# GSM_SOM.net
KiCad netlist of a schematic drawn in Altium Designer
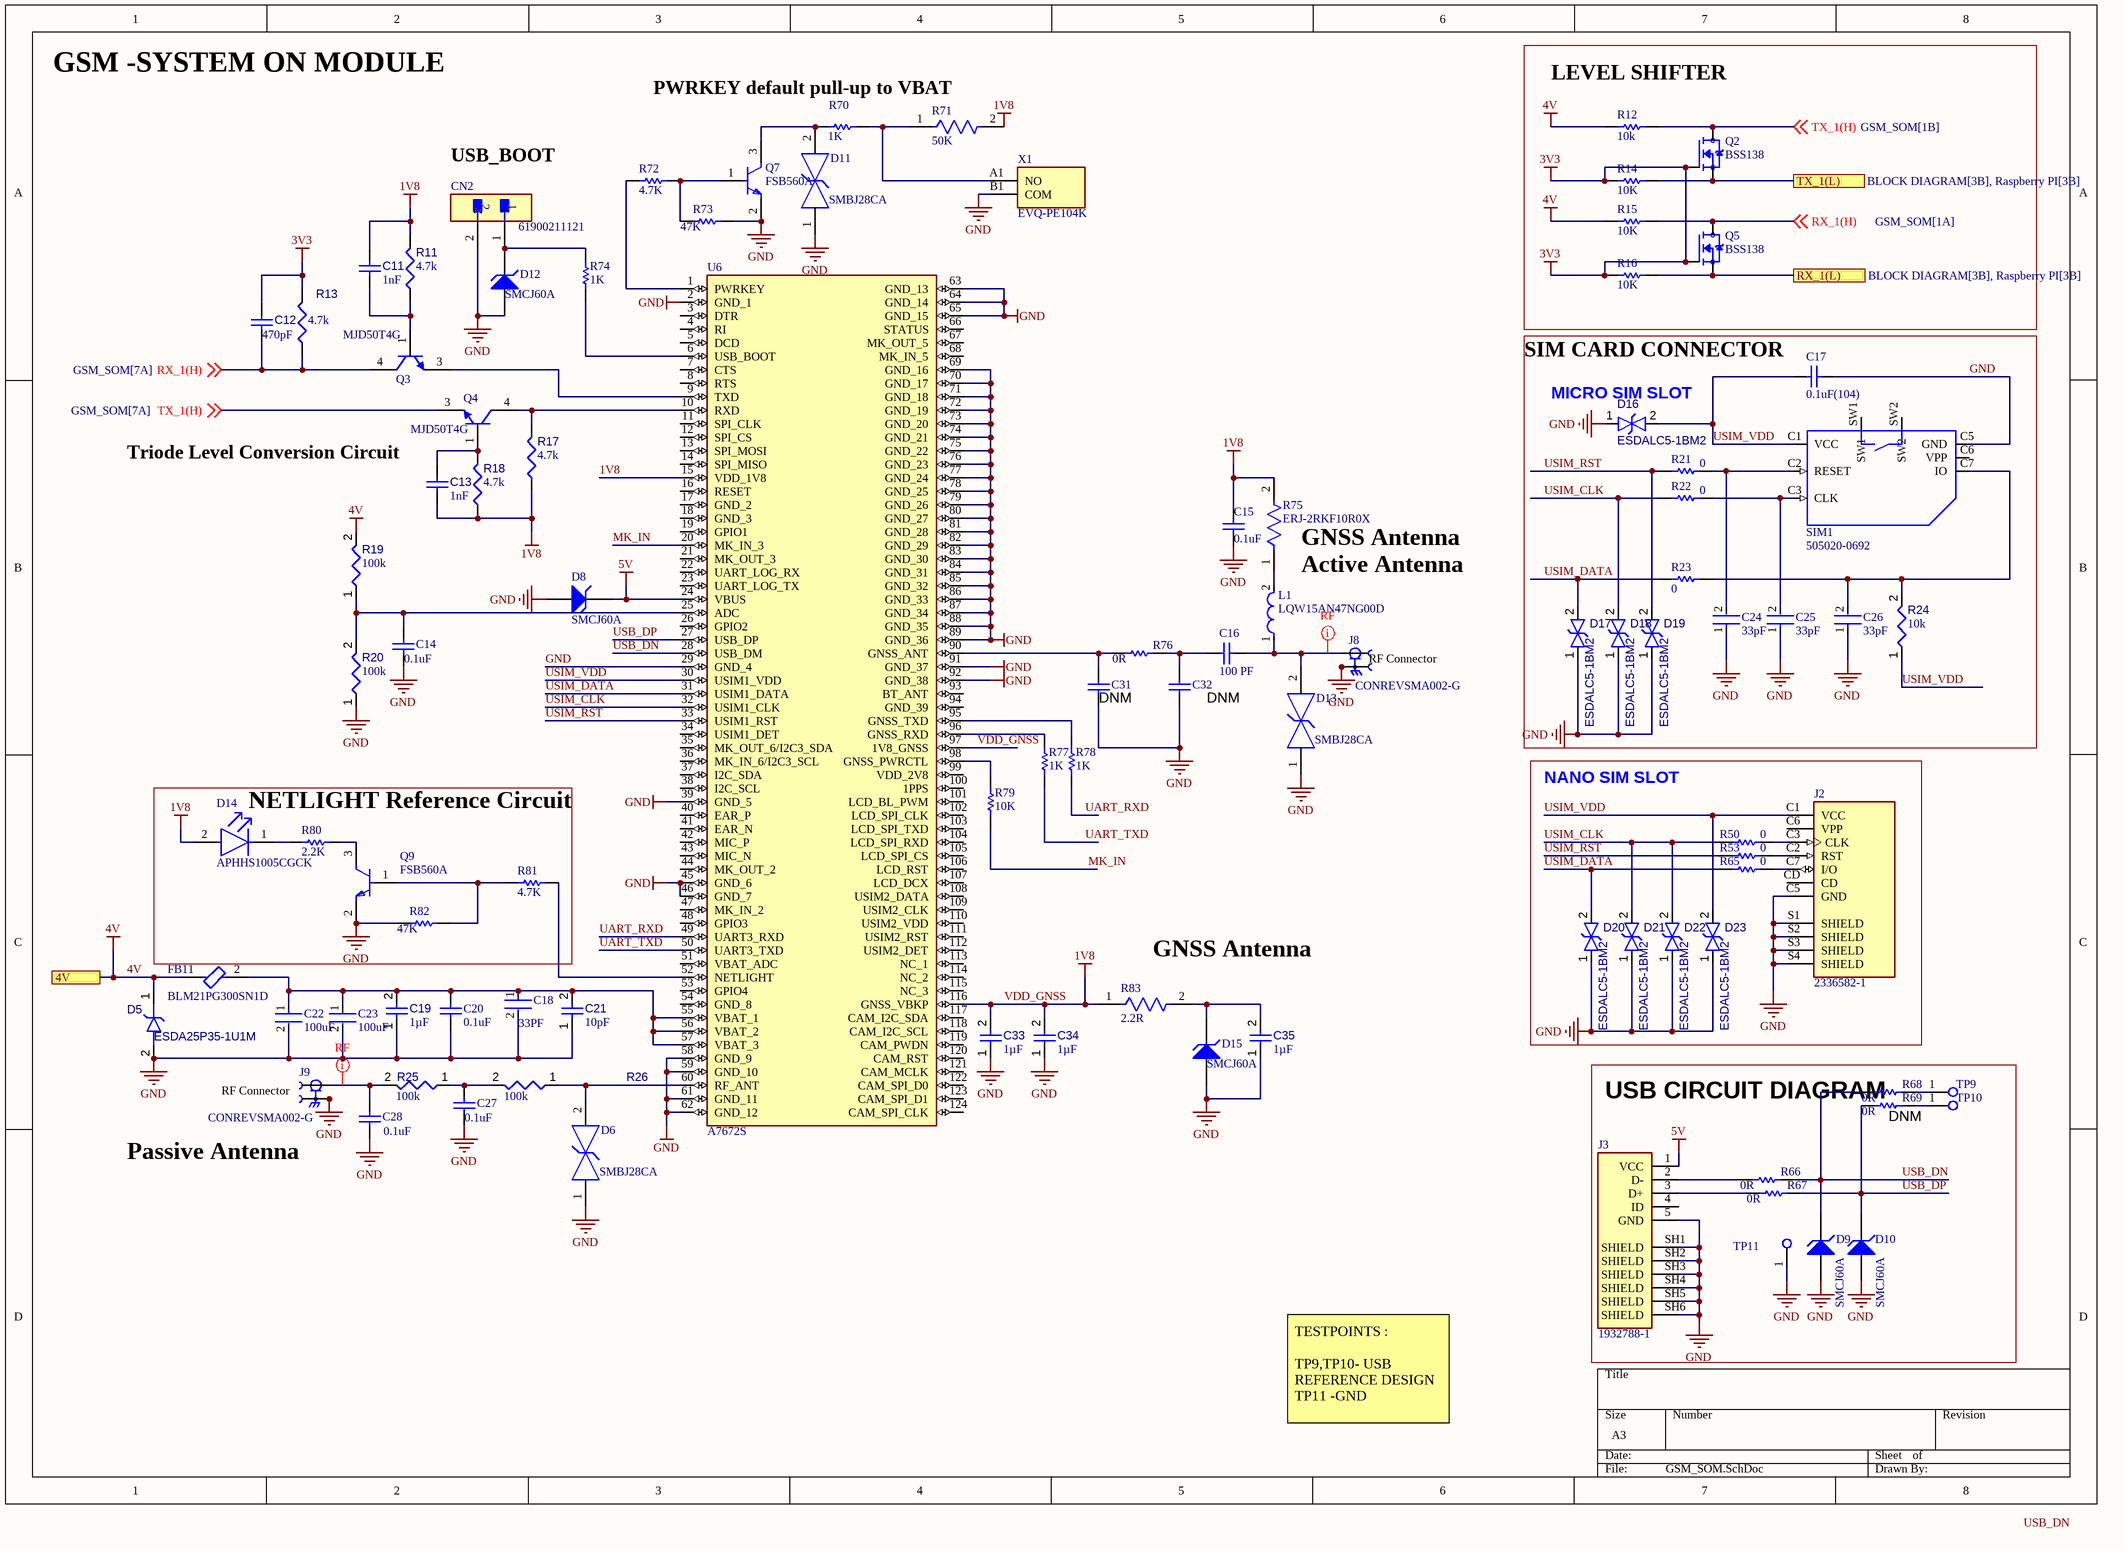
[diagram p0: GSM_SOM.SchDoc]

(export (version "E")
  (design (tool "Eeschema 10.0.6"))
  (components
    (comp (ref "C11")
      (value "1nF")
      (footprint "CAPC0402(1005)33_L")
      (description "Chip Capacitor, 1nF +/-20%, 50V, 0402, Thickness 0.33 mm")
      (fields (field (name "TOLERANCE") "10%") (field (name "Comment") "Capacitor 1nF +/-20% 50V 0402"))
      (libsource (lib "Bannari Amman Institute of Technology") (part "CAP-NP-2"))
    )
    (comp (ref "C12")
      (value "470pF")
      (footprint "CAPC0402(1005)60_L")
      (description "Chip Capacitor, 470pF +/-20%, 50V, 0402, Thickness 0.6 mm")
      (fields (field (name "TOLERANCE") "20%") (field (name "Comment") "Capacitor 470pF +/-20% 50V 0402"))
      (libsource (lib "Bannari Amman Institute of Technology") (part "CAP-NP-2"))
    )
    (comp (ref "C13")
      (value "1nF")
      (footprint "CAPC0402(1005)33_L")
      (description "Chip Capacitor, 1nF +/-20%, 50V, 0402, Thickness 0.33 mm")
      (fields (field (name "TOLERANCE") "10%") (field (name "Comment") "Capacitor 1nF +/-20% 50V 0402"))
      (libsource (lib "Bannari Amman Institute of Technology") (part "CAP-NP-2"))
    )
    (comp (ref "C14")
      (value "0.1uF")
      (footprint "CAPC1005X55X30LL05T10")
      (fields (field (name "MANUFACTURER") "Kemet") (field (name "PART NUMBER") "C0402C104K4RACTU"))
      (libsource (lib "Altium Content Vault") (part "CAP"))
    )
    (comp (ref "C15")
      (value "0.1uF")
      (footprint "CAPC1005X55X30LL05T10")
      (fields (field (name "MANUFACTURER") "Kemet") (field (name "PART NUMBER") "C0402C104K4RACTU"))
      (libsource (lib "Altium Content Vault") (part "CAP"))
    )
    (comp (ref "C16")
      (value "100 PF")
      (footprint "CAPC1005X55X25ML05T10")
      (fields (field (name "MANUFACTURER") "Murata") (field (name "PART NUMBER") "GRM1555C1H101JA01D"))
      (libsource (lib "Altium Content Vault") (part "CAP"))
    )
    (comp (ref "C17")
      (value "0.1uF(104)")
      (footprint "CAPC1005X55X30LL05T10")
      (fields (field (name "MANUFACTURER") "Kemet") (field (name "PART NUMBER") "C0402C104K4RACTU"))
      (libsource (lib "Altium Content Vault") (part "CAP"))
    )
    (comp (ref "C18")
      (value "33PF")
      (footprint "FP-0402-L_1_0_1-W_0_5_0_1-IPC_A")
      (description "General Purpose Ceramic Capacitor, 0402, 33pF, 5%, C0G, 30ppm/°C, 50V")
      (fields (field (name "TOLERANCE") "5%") (field (name "VOLTAGE") "50V"))
      (libsource (lib "Altium Content Vault") (part "b4654b650e69147ec39a6b967a45e02"))
    )
    (comp (ref "C19")
      (value "1µF")
      (footprint "CAPC0402(1005)60_L")
      (description "Chip Capacitor, 1µF +/-20%, 10V, 0402, Thickness 0.6 mm")
      (fields (field (name "TOLERANCE") "10%") (field (name "Comment") "Capacitor 1µF +/-20% 10V 0402"))
      (libsource (lib "") (part "CAP-NP-2_1"))
    )
    (comp (ref "C20")
      (value "0.1uF")
      (footprint "CAPC1005X55X30LL05T10")
      (fields (field (name "MANUFACTURER") "Kemet") (field (name "PART NUMBER") "C0402C104K4RACTU"))
      (libsource (lib "Altium Content Vault") (part "CAP"))
    )
    (comp (ref "C21")
      (value "10pF")
      (footprint "CAPC1005X55X30LL05T10")
      (description "Chip Capacitor, 10 pF, +/- 0.25 pF, 50 V, 0402 (1005 Metric)")
      (fields
        (field (name "TOLERANCE") "0.25%")
        (field (name "Comment") "Capacitor 10 pF +/- 0.25 pF 50 V 0402")
      )
      (libsource (lib "") (part "CAP-NP-2_1"))
    )
    (comp (ref "C22")
      (value "100uF")
      (footprint "FP-GRM32-0_3-MFG")
      (description "CAP CER 100UF 6.3V X5R 1210")
      (fields
        (field (name "OCTOPART") "https://octopart.com/grm32er60j107me20l-murata-197007")
        (field (name "3DS PART NUMBER") "220-00002")
      )
      (libsource (lib "Altium Content Vault") (part "11868f565c42a9108669ba33697ecf6"))
    )
    (comp (ref "C23")
      (value "100uF")
      (footprint "FP-GRM32-0_3-MFG")
      (description "CAP CER 100UF 6.3V X5R 1210")
      (fields
        (field (name "OCTOPART") "https://octopart.com/grm32er60j107me20l-murata-197007")
        (field (name "3DS PART NUMBER") "220-00002")
      )
      (libsource (lib "Altium Content Vault") (part "11868f565c42a9108669ba33697ecf6"))
    )
    (comp (ref "C24")
      (value "33pF")
      (footprint "FP-0402-L_1_0_1-W_0_5_0_1-IPC_A")
      (description "General Purpose Ceramic Capacitor, 0402, 33pF, 5%, C0G, 30ppm/°C, 50V")
      (fields (field (name "TOLERANCE") "5%") (field (name "VOLTAGE") "50V"))
      (libsource (lib "Altium Content Vault") (part "b4654b650e69147ec39a6b967a45e02"))
    )
    (comp (ref "C25")
      (value "33pF")
      (footprint "FP-0402-L_1_0_1-W_0_5_0_1-IPC_A")
      (description "General Purpose Ceramic Capacitor, 0402, 33pF, 5%, C0G, 30ppm/°C, 50V")
      (fields (field (name "TOLERANCE") "5%") (field (name "VOLTAGE") "50V"))
      (libsource (lib "Altium Content Vault") (part "b4654b650e69147ec39a6b967a45e02"))
    )
    (comp (ref "C26")
      (value "33pF")
      (footprint "FP-0402-L_1_0_1-W_0_5_0_1-IPC_A")
      (description "General Purpose Ceramic Capacitor, 0402, 33pF, 5%, C0G, 30ppm/°C, 50V")
      (fields (field (name "TOLERANCE") "5%") (field (name "VOLTAGE") "50V"))
      (libsource (lib "Altium Content Vault") (part "b4654b650e69147ec39a6b967a45e02"))
    )
    (comp (ref "C27")
      (value "0.1uF")
      (footprint "CAPC1005X55X30LL05T10")
      (fields (field (name "MANUFACTURER") "Kemet") (field (name "PART NUMBER") "C0402C104K4RACTU"))
      (libsource (lib "Altium Content Vault") (part "CAP"))
    )
    (comp (ref "C28")
      (value "0.1uF")
      (footprint "CAPC1005X55X30LL05T10")
      (fields (field (name "MANUFACTURER") "Kemet") (field (name "PART NUMBER") "C0402C104K4RACTU"))
      (libsource (lib "Altium Content Vault") (part "CAP"))
    )
    (comp (ref "C31")
      (value "0.1uF")
      (footprint "CAPC1005X55X30LL05T10")
      (fields (field (name "MANUFACTURER") "Kemet") (field (name "PART NUMBER") "C0402C104K4RACTU"))
      (libsource (lib "Altium Content Vault") (part "CAP"))
    )
    (comp (ref "C32")
      (value "0.1uF")
      (footprint "CAPC1005X55X30LL05T10")
      (fields (field (name "MANUFACTURER") "Kemet") (field (name "PART NUMBER") "C0402C104K4RACTU"))
      (libsource (lib "Altium Content Vault") (part "CAP"))
    )
    (comp (ref "C33")
      (value "1µF")
      (footprint "CAPC0402(1005)60_L")
      (description "Chip Capacitor, 1µF +/-20%, 10V, 0402, Thickness 0.6 mm")
      (fields (field (name "TOLERANCE") "10%") (field (name "Comment") "Capacitor 1µF +/-20% 10V 0402"))
      (libsource (lib "") (part "CAP-NP-2_1"))
    )
    (comp (ref "C34")
      (value "1µF")
      (footprint "CAPC0402(1005)60_L")
      (description "Chip Capacitor, 1µF +/-20%, 10V, 0402, Thickness 0.6 mm")
      (fields (field (name "TOLERANCE") "10%") (field (name "Comment") "Capacitor 1µF +/-20% 10V 0402"))
      (libsource (lib "") (part "CAP-NP-2_1"))
    )
    (comp (ref "C35")
      (value "1µF")
      (footprint "CAPC0402(1005)60_L")
      (description "Chip Capacitor, 1µF +/-20%, 10V, 0402, Thickness 0.6 mm")
      (fields (field (name "TOLERANCE") "10%") (field (name "Comment") "Capacitor 1µF +/-20% 10V 0402"))
      (libsource (lib "") (part "CAP-NP-2_1"))
    )
    (comp (ref "CN2")
      (value "61900211121")
      (footprint "FP-61900211121-MFG")
      (description "CONN HEADER VERT 2POS 2.54MM")
      (libsource (lib "Altium Content Vault") (part "3bc925449376181038e59eaffc5286c"))
    )
    (comp (ref "D5")
      (value "ESDA25P35-1U1M")
      (footprint "STM-QFN1610")
      (description "TVS DIODE 22V 41V 1610")
      (libsource (lib "Bannari Amman Institute of Technology") (part "D-TVS-AK-2"))
    )
    (comp (ref "D6")
      (value "SMBJ28CA")
      (footprint "FP-SMBJ-CA-MFG")
      (description "TVS DIODE 28V 45.4V DO214AA")
      (fields
        (field (name "MANUFACTURER") "Littelfuse Inc")
        (field (name "OCTOPART") "https://octopart.com/smbj28ca-littelfuse-350757")
      )
      (libsource (lib "Altium Content Vault") (part "89c663e49c8877d2c9d183c2997548d"))
    )
    (comp (ref "D8")
      (value "SMCJ60A")
      (footprint "LFUS-DO-214AB-2_V")
      (fields (field (name "MANUFACTURER") "Littelfuse"))
      (libsource (lib "Altium Content Vault") (part "DZEN-AK-2"))
    )
    (comp (ref "D9")
      (value "SMCJ60A")
      (footprint "LFUS-DO-214AB-2_V")
      (fields (field (name "MANUFACTURER") "Littelfuse"))
      (libsource (lib "Altium Content Vault") (part "DZEN-AK-2"))
    )
    (comp (ref "D10")
      (value "SMCJ60A")
      (footprint "LFUS-DO-214AB-2_V")
      (fields (field (name "MANUFACTURER") "Littelfuse"))
      (libsource (lib "Altium Content Vault") (part "DZEN-AK-2"))
    )
    (comp (ref "D11")
      (value "SMBJ28CA")
      (footprint "FP-SMBJ-CA-MFG")
      (description "TVS DIODE 28V 45.4V DO214AA")
      (fields
        (field (name "MANUFACTURER") "Littelfuse Inc")
        (field (name "OCTOPART") "https://octopart.com/smbj28ca-littelfuse-350757")
      )
      (libsource (lib "Altium Content Vault") (part "89c663e49c8877d2c9d183c2997548d"))
    )
    (comp (ref "D12")
      (value "SMCJ60A")
      (footprint "LFUS-DO-214AB-2_V")
      (fields (field (name "MANUFACTURER") "Littelfuse"))
      (libsource (lib "Altium Content Vault") (part "DZEN-AK-2"))
    )
    (comp (ref "D13")
      (value "SMBJ28CA")
      (footprint "FP-SMBJ-CA-MFG")
      (description "TVS DIODE 28V 45.4V DO214AA")
      (fields
        (field (name "MANUFACTURER") "Littelfuse Inc")
        (field (name "OCTOPART") "https://octopart.com/smbj28ca-littelfuse-350757")
      )
      (libsource (lib "Altium Content Vault") (part "89c663e49c8877d2c9d183c2997548d"))
    )
    (comp (ref "D14")
      (value "APHHS1005CGCK")
      (footprint "FP-APHHS1005CGCK-MFG")
      (description "LED GREEN CLEAR CHIP SMD")
      (libsource (lib "Altium Content Vault") (part "8706943c75ba83719d021d2fdc84c58"))
    )
    (comp (ref "D15")
      (value "SMCJ60A")
      (footprint "LFUS-DO-214AB-2_V")
      (fields (field (name "MANUFACTURER") "Littelfuse"))
      (libsource (lib "Altium Content Vault") (part "DZEN-AK-2"))
    )
    (comp (ref "D16")
      (value "ESDALC5-1BM2")
      (footprint "STM-SOD-882_V")
      (description "Single Line Low Capacitance Transil™, 5 V, -55 to 150 degC, 2-Pin SOD-882, RoHS, Tape and Reel")
      (libsource (lib "Bannari Amman Institute of Technology") (part "D-TVS-AA-2"))
    )
    (comp (ref "D17")
      (value "ESDALC5-1BM2")
      (footprint "STM-SOD-882_V")
      (description "Single Line Low Capacitance Transil™, 5 V, -55 to 150 degC, 2-Pin SOD-882, RoHS, Tape and Reel")
      (libsource (lib "Bannari Amman Institute of Technology") (part "D-TVS-AA-2"))
    )
    (comp (ref "D18")
      (value "ESDALC5-1BM2")
      (footprint "STM-SOD-882_V")
      (description "Single Line Low Capacitance Transil™, 5 V, -55 to 150 degC, 2-Pin SOD-882, RoHS, Tape and Reel")
      (libsource (lib "Bannari Amman Institute of Technology") (part "D-TVS-AA-2"))
    )
    (comp (ref "D19")
      (value "ESDALC5-1BM2")
      (footprint "STM-SOD-882_V")
      (description "Single Line Low Capacitance Transil™, 5 V, -55 to 150 degC, 2-Pin SOD-882, RoHS, Tape and Reel")
      (libsource (lib "Bannari Amman Institute of Technology") (part "D-TVS-AA-2"))
    )
    (comp (ref "D20")
      (value "ESDALC5-1BM2")
      (footprint "STM-SOD-882_V")
      (description "Single Line Low Capacitance Transil™, 5 V, -55 to 150 degC, 2-Pin SOD-882, RoHS, Tape and Reel")
      (libsource (lib "Bannari Amman Institute of Technology") (part "D-TVS-AA-2"))
    )
    (comp (ref "D21")
      (value "ESDALC5-1BM2")
      (footprint "STM-SOD-882_V")
      (description "Single Line Low Capacitance Transil™, 5 V, -55 to 150 degC, 2-Pin SOD-882, RoHS, Tape and Reel")
      (libsource (lib "Bannari Amman Institute of Technology") (part "D-TVS-AA-2"))
    )
    (comp (ref "D22")
      (value "ESDALC5-1BM2")
      (footprint "STM-SOD-882_V")
      (description "Single Line Low Capacitance Transil™, 5 V, -55 to 150 degC, 2-Pin SOD-882, RoHS, Tape and Reel")
      (libsource (lib "Bannari Amman Institute of Technology") (part "D-TVS-AA-2"))
    )
    (comp (ref "D23")
      (value "ESDALC5-1BM2")
      (footprint "STM-SOD-882_V")
      (description "Single Line Low Capacitance Transil™, 5 V, -55 to 150 degC, 2-Pin SOD-882, RoHS, Tape and Reel")
      (libsource (lib "Bannari Amman Institute of Technology") (part "D-TVS-AA-2"))
    )
    (comp (ref "FB1")
      (value "BLM21PG300SN1D")
      (footprint "FP-BLM21-0_2-t0_85-e0_5-d-MFG")
      (description "Chip Ferrite Bead, 0805, 30Ω @ 100MHz, 0.014Ω, , 4A")
      (fields (field (name "TOLERANCE") "25%"))
      (libsource (lib "Altium Content Vault") (part "5f30dd21d616792df468990f7003faa"))
    )
    (comp (ref "J2")
      (value "2336582-1")
      (footprint "TE_2336582-1")
      (description "PUSH-PUSH NANO SIM CONNECTOR")
      (libsource (lib "2336582-1") (part "2336582-1"))
    )
    (comp (ref "J3")
      (value "1932788-1")
      (footprint "TE_1932788-1")
      (libsource (lib "1932788-1") (part "1932788-1"))
    )
    (comp (ref "J8")
      (value "CONREVSMA002-G")
      (footprint "LINX_CONREVSMA002-G")
      (description "RP-SMA Female Right-Angle Through-Hole Mount Connector, Gold")
      (fields (field (name "MF") "Linx Technologies"))
      (libsource (lib "") (part "CONREVSMA002-G_1"))
    )
    (comp (ref "J9")
      (value "CONREVSMA002-G")
      (footprint "LINX_CONREVSMA002-G")
      (description "RP-SMA Female Right-Angle Through-Hole Mount Connector, Gold")
      (fields (field (name "MF") "Linx Technologies"))
      (libsource (lib "CONREVSMA002-G") (part "CONREVSMA002-G"))
    )
    (comp (ref "L1")
      (value "LQW15AN47NG00D")
      (footprint "FP-LQW15AN_00-W0_5-0_1-MFG")
      (description "Wire Wound RF Inductor 47nH ±2% 210mA 1.08Ω 0402 (1005)")
      (fields (field (name "TOLERANCE") "2%"))
      (libsource (lib "Altium Content Vault") (part "725321dda6339637d4d059423bc1c3c"))
    )
    (comp (ref "Q2")
      (value "BSS138")
      (footprint "SOT95P240X111-3N")
      (description "N-Channel 50V 220mA (Ta) 360mW (Ta) Surface Mount SOT-23-3")
      (fields (field (name "MF") "ON Semiconductor"))
      (libsource (lib "BSS138") (part "BSS138"))
    )
    (comp (ref "Q3")
      (value "MJD50T4G")
      (footprint "ONSC-DPAK-3-369C-01_V")
      (description "High Voltage Power Transistor, 3-Pin DPAK, Pb-Free, Tape and Reel")
      (fields (field (name "MANUFACTURER") "On Semiconductor"))
      (libsource (lib "Altium Content Vault") (part "ONSC-NPN-B1E3C4-3"))
    )
    (comp (ref "Q4")
      (value "MJD50T4G")
      (footprint "ONSC-DPAK-3-369C-01_V")
      (description "High Voltage Power Transistor, 3-Pin DPAK, Pb-Free, Tape and Reel")
      (fields (field (name "MANUFACTURER") "On Semiconductor"))
      (libsource (lib "Altium Content Vault") (part "ONSC-NPN-B1E3C4-3"))
    )
    (comp (ref "Q5")
      (value "BSS138")
      (footprint "SOT95P240X111-3N")
      (description "N-Channel 50V 220mA (Ta) 360mW (Ta) Surface Mount SOT-23-3")
      (fields (field (name "MF") "ON Semiconductor"))
      (libsource (lib "BSS138") (part "BSS138"))
    )
    (comp (ref "Q7")
      (value "FSB560A")
      (footprint "FP-527AG-MFG")
      (description "FSB560A Bipolar Transistors - BJT NPN Transistor Low Saturation")
      (libsource (lib "Altium Content Vault") (part "b44e953556f554d0102664c7d152cb4"))
    )
    (comp (ref "Q9")
      (value "FSB560A")
      (footprint "FP-527AG-MFG")
      (description "FSB560A Bipolar Transistors - BJT NPN Transistor Low Saturation")
      (libsource (lib "Altium Content Vault") (part "b44e953556f554d0102664c7d152cb4"))
    )
    (comp (ref "R11")
      (value "4.7k")
      (footprint "RESC1005X40X25ML05T05")
      (description "Chip Resistor, 4.7 KOhm, +/- 1%, 0.1 W, -55 to 155 degC, 0402 (1005 Metric)")
      (fields (field (name "POWER") "100mW") (field (name "TOLERANCE") "1%"))
      (libsource (lib "Bannari Amman Institute of Technology") (part "RES-2"))
    )
    (comp (ref "R12")
      (value "10k")
      (footprint "RESC1005X40X25LL05T10")
      (fields (field (name "PART NUMBER") "RC0402FR-0710KL") (field (name "MANUFACTURER") "Yageo / Phycomp"))
      (libsource (lib "Altium Content Vault") (part "RES"))
    )
    (comp (ref "R13")
      (value "4.7k")
      (footprint "RESC1005X40X25ML05T05")
      (description "Chip Resistor, 4.7 KOhm, +/- 1%, 0.1 W, -55 to 155 degC, 0402 (1005 Metric)")
      (fields (field (name "POWER") "100mW") (field (name "TOLERANCE") "1%"))
      (libsource (lib "Bannari Amman Institute of Technology") (part "RES-2"))
    )
    (comp (ref "R14")
      (value "10K")
      (footprint "RESC1005X40X25LL05T10")
      (fields (field (name "PART NUMBER") "RC0402FR-0710KL") (field (name "MANUFACTURER") "Yageo / Phycomp"))
      (libsource (lib "Altium Content Vault") (part "RES"))
    )
    (comp (ref "R15")
      (value "10K")
      (footprint "RESC1005X40X25LL05T10")
      (fields (field (name "PART NUMBER") "RC0402FR-0710KL") (field (name "MANUFACTURER") "Yageo / Phycomp"))
      (libsource (lib "Altium Content Vault") (part "RES"))
    )
    (comp (ref "R16")
      (value "10K")
      (footprint "RESC1005X40X25LL05T10")
      (fields (field (name "PART NUMBER") "RC0402FR-0710KL") (field (name "MANUFACTURER") "Yageo / Phycomp"))
      (libsource (lib "Altium Content Vault") (part "RES"))
    )
    (comp (ref "R17")
      (value "4.7k")
      (footprint "RESC1005X40X25ML05T05")
      (description "Chip Resistor, 4.7 KOhm, +/- 1%, 0.1 W, -55 to 155 degC, 0402 (1005 Metric)")
      (fields (field (name "POWER") "100mW") (field (name "TOLERANCE") "1%"))
      (libsource (lib "Bannari Amman Institute of Technology") (part "RES-2"))
    )
    (comp (ref "R18")
      (value "4.7k")
      (footprint "RESC1005X40X25ML05T05")
      (description "Chip Resistor, 4.7 KOhm, +/- 1%, 0.1 W, -55 to 155 degC, 0402 (1005 Metric)")
      (fields (field (name "POWER") "100mW") (field (name "TOLERANCE") "1%"))
      (libsource (lib "Bannari Amman Institute of Technology") (part "RES-2"))
    )
    (comp (ref "R19")
      (value "100k")
      (footprint "RESC0402(1005)_L")
      (description "Chip Resistor, 100 kOhms, +/-1 %, 63 mW, -55 to 155 degC, 0402")
      (fields (field (name "TOLERANCE") "1%") (field (name "POWER") "63mW"))
      (libsource (lib "") (part "RES-2_1"))
    )
    (comp (ref "R20")
      (value "100k")
      (footprint "RESC0402(1005)_L")
      (description "Chip Resistor, 100 kOhms, +/-1 %, 63 mW, -55 to 155 degC, 0402")
      (fields (field (name "TOLERANCE") "1%") (field (name "POWER") "63mW"))
      (libsource (lib "") (part "RES-2_1"))
    )
    (comp (ref "R21")
      (value "0")
      (footprint "RESC1005X40X25ML05T10")
      (description "Chip Resistor, 0 Ohm, 0.063 W, -55 to 155 degC, 0402 (1005 Metric)")
      (fields (field (name "POWER") "63mW") (field (name "Comment") "Resistor 0R 0402 63 mW"))
      (libsource (lib "") (part "RES-2_2"))
    )
    (comp (ref "R22")
      (value "0")
      (footprint "RESC1005X40X25ML05T10")
      (description "Chip Resistor, 0 Ohm, 0.063 W, -55 to 155 degC, 0402 (1005 Metric)")
      (fields (field (name "POWER") "63mW") (field (name "Comment") "Resistor 0R 0402 63 mW"))
      (libsource (lib "") (part "RES-2_2"))
    )
    (comp (ref "R23")
      (value "0")
      (footprint "RESC1005X40X25ML05T10")
      (description "Chip Resistor, 0 Ohm, 0.063 W, -55 to 155 degC, 0402 (1005 Metric)")
      (fields (field (name "POWER") "63mW") (field (name "Comment") "Resistor 0R 0402 63 mW"))
      (libsource (lib "") (part "RES-2_2"))
    )
    (comp (ref "R24")
      (value "10k")
      (footprint "RESC1005X40X25ML05T05")
      (description "Chip Resistor, 10 KOhm, +/- 1%, 0.1 W, -55 to 155 degC, 0402 (1005 Metric)")
      (fields (field (name "TOLERANCE") "1%") (field (name "POWER") "100mW"))
      (libsource (lib "") (part "RES-2_1"))
    )
    (comp (ref "R25")
      (value "100k")
      (footprint "RESC0402(1005)_L")
      (description "Chip Resistor, 100 kOhms, +/-1 %, 63 mW, -55 to 155 degC, 0402")
      (fields (field (name "TOLERANCE") "1%") (field (name "POWER") "63mW"))
      (libsource (lib "") (part "RES-2_1"))
    )
    (comp (ref "R26")
      (value "100k")
      (footprint "RESC0402(1005)_L")
      (description "Chip Resistor, 100 kOhms, +/-1 %, 63 mW, -55 to 155 degC, 0402")
      (fields (field (name "TOLERANCE") "1%") (field (name "POWER") "63mW"))
      (libsource (lib "") (part "RES-2_1"))
    )
    (comp (ref "R50")
      (value "0")
      (footprint "RESC1005X40X25ML05T10")
      (description "Chip Resistor, 0 Ohm, 0.063 W, -55 to 155 degC, 0402 (1005 Metric)")
      (fields (field (name "POWER") "63mW") (field (name "Comment") "Resistor 0R 0402 63 mW"))
      (libsource (lib "") (part "RES-2_2"))
    )
    (comp (ref "R53")
      (value "0")
      (footprint "RESC1005X40X25ML05T10")
      (description "Chip Resistor, 0 Ohm, 0.063 W, -55 to 155 degC, 0402 (1005 Metric)")
      (fields (field (name "POWER") "63mW") (field (name "Comment") "Resistor 0R 0402 63 mW"))
      (libsource (lib "") (part "RES-2_2"))
    )
    (comp (ref "R65")
      (value "0")
      (footprint "RESC1005X40X25ML05T10")
      (description "Chip Resistor, 0 Ohm, 0.063 W, -55 to 155 degC, 0402 (1005 Metric)")
      (fields (field (name "POWER") "63mW") (field (name "Comment") "Resistor 0R 0402 63 mW"))
      (libsource (lib "") (part "RES-2_2"))
    )
    (comp (ref "R66")
      (value "0R")
      (footprint "RESC1005X40X25NL05T10")
      (fields (field (name "MANUFACTURER") "Yageo / Phycomp") (field (name "PART NUMBER") "RC0402JR-070RL"))
      (libsource (lib "Altium Content Vault") (part "RES"))
    )
    (comp (ref "R67")
      (value "0R")
      (footprint "RESC1005X40X25NL05T10")
      (fields (field (name "MANUFACTURER") "Yageo / Phycomp") (field (name "PART NUMBER") "RC0402JR-070RL"))
      (libsource (lib "Altium Content Vault") (part "RES"))
    )
    (comp (ref "R68")
      (value "0R")
      (footprint "RESC1005X40X25NL05T10")
      (fields (field (name "MANUFACTURER") "Yageo / Phycomp") (field (name "PART NUMBER") "RC0402JR-070RL"))
      (libsource (lib "Altium Content Vault") (part "RES"))
    )
    (comp (ref "R69")
      (value "0R")
      (footprint "RESC1005X40X25NL05T10")
      (fields (field (name "MANUFACTURER") "Yageo / Phycomp") (field (name "PART NUMBER") "RC0402JR-070RL"))
      (libsource (lib "Altium Content Vault") (part "RES"))
    )
    (comp (ref "R70")
      (value "1K")
      (footprint "RESC1005X40X25NL05T05")
      (description "Chip Resistor, 1 KOhm, +/- 1%, 100 mW, -55 to 155 degC, 0402 (1005 Metric), RoHS, Tape and Reel")
      (fields (field (name "PARTNUMBER") "ERJ-2RKF1001X") (field (name "MANUFACTURER") "Basic Passives"))
      (libsource (lib "Altium Content Vault") (part "RES-2"))
    )
    (comp (ref "R71")
      (value "50K")
      (footprint "FP-CRCW0402-e3-IPC_A")
      (description "RES Thick Film, 50kΩ, 1%, 0.063W, 100ppm/°C, 0402")
      (fields (field (name "TOLERANCE") "1%"))
      (libsource (lib "Altium Content Vault") (part "1029c3af85768c4190bb7ad29bc67b5"))
    )
    (comp (ref "R72")
      (value "4.7K")
      (footprint "RESC1005X40X25LL05T05")
      (description "Chip Resistor, 4.7 KOhm, +/- 1%, 0.1 W, -55 to 155 degC, 0402 (1005 Metric), RoHS, Tape and Reel")
      (fields (field (name "TOLERANCE") "1%") (field (name "PARTNUMBER") "ERJ-2RKF4701X"))
      (libsource (lib "Altium Content Vault") (part "RES-2"))
    )
    (comp (ref "R73")
      (value "47K")
      (footprint "RESC1005X40X25ML05T10")
      (fields (field (name "PART NUMBER") "RC0402FR-0747KL") (field (name "MANUFACTURER") "Yageo / Phycomp"))
      (libsource (lib "Altium Content Vault") (part "RES"))
    )
    (comp (ref "R74")
      (value "1K")
      (footprint "RESC1005X40X25NL05T05")
      (description "Chip Resistor, 1 KOhm, +/- 1%, 100 mW, -55 to 155 degC, 0402 (1005 Metric), RoHS, Tape and Reel")
      (fields (field (name "PARTNUMBER") "ERJ-2RKF1001X") (field (name "MANUFACTURER") "Basic Passives"))
      (libsource (lib "Altium Content Vault") (part "RES-2"))
    )
    (comp (ref "R75")
      (value "ERJ-2RKF10R0X")
      (footprint "FP-ERJ2RK-MFG")
      (description "RES SMD 10 OHM 1% 1/10W 0402")
      (fields
        (field (name "OCTOPART") "https://octopart.com/erj-2rkf10r0x-panasonic-55404982")
        (field (name "MANUFACTURER") "Panasonic")
      )
      (libsource (lib "Altium Content Vault") (part "1029c3af85768c4190bb7ad29bc67b5"))
    )
    (comp (ref "R76")
      (value "0R")
      (footprint "RESC1005X40X25NL05T10")
      (fields (field (name "MANUFACTURER") "Yageo / Phycomp") (field (name "PART NUMBER") "RC0402JR-070RL"))
      (libsource (lib "Altium Content Vault") (part "RES"))
    )
    (comp (ref "R77")
      (value "1K")
      (footprint "RESC1005X40X25NL05T05")
      (description "Chip Resistor, 1 KOhm, +/- 1%, 100 mW, -55 to 155 degC, 0402 (1005 Metric), RoHS, Tape and Reel")
      (fields (field (name "PARTNUMBER") "ERJ-2RKF1001X") (field (name "MANUFACTURER") "Basic Passives"))
      (libsource (lib "Altium Content Vault") (part "RES-2"))
    )
    (comp (ref "R78")
      (value "1K")
      (footprint "RESC1005X40X25NL05T05")
      (description "Chip Resistor, 1 KOhm, +/- 1%, 100 mW, -55 to 155 degC, 0402 (1005 Metric), RoHS, Tape and Reel")
      (fields (field (name "PARTNUMBER") "ERJ-2RKF1001X") (field (name "MANUFACTURER") "Basic Passives"))
      (libsource (lib "Altium Content Vault") (part "RES-2"))
    )
    (comp (ref "R79")
      (value "10K")
      (footprint "RESC1005X40X25LL05T05")
      (description "Chip Resistor, 10 KOhm, +/- 1%, 0.1 W, -55 to 155 degC, 0402 (1005 Metric), RoHS, Tape and Reel")
      (fields (field (name "TOLERANCE") "1%") (field (name "MANUFACTURER") "Panasonic"))
      (libsource (lib "Altium Content Vault") (part "RES-2"))
    )
    (comp (ref "R80")
      (value "2.2K")
      (footprint "RESC1005X40X25NL05T10")
      (fields (field (name "MANUFACTURER") "Yageo / Phycomp") (field (name "PART NUMBER") "RC0402FR-072K2L"))
      (libsource (lib "Altium Content Vault") (part "RES"))
    )
    (comp (ref "R81")
      (value "4.7K")
      (footprint "RESC1005X40X25LL05T05")
      (description "Chip Resistor, 4.7 KOhm, +/- 1%, 0.1 W, -55 to 155 degC, 0402 (1005 Metric), RoHS, Tape and Reel")
      (fields (field (name "TOLERANCE") "1%") (field (name "PARTNUMBER") "ERJ-2RKF4701X"))
      (libsource (lib "Altium Content Vault") (part "RES-2"))
    )
    (comp (ref "R82")
      (value "47K")
      (footprint "RESC1005X40X25ML05T10")
      (fields (field (name "PART NUMBER") "RC0402FR-0747KL") (field (name "MANUFACTURER") "Yageo / Phycomp"))
      (libsource (lib "Altium Content Vault") (part "RES"))
    )
    (comp (ref "R83")
      (value "2.2R")
      (footprint "FP-CRCW0402-e3-IPC_C")
      (description "RES Thick Film, 2.2Ω, 1%, 0.063W, 100ppm/°C, 0402")
      (fields (field (name "TOLERANCE") "1%"))
      (libsource (lib "Altium Content Vault") (part "1029c3af85768c4190bb7ad29bc67b5"))
    )
    (comp (ref "SIM1")
      (value "505020-0692")
      (footprint "505020-0692")
      (description "6 Position Card Connector Micro SIM Surface Mount, Right Angle Gold")
      (fields (field (name "MF") "Molex") (field (name "MP") "5050200692"))
      (libsource (lib "505020-0692") (part "505020-0692"))
    )
    (comp (ref "TP9")
      (value "Test Point")
      (footprint "TEST_POINT_SMD_30D")
      (description "TEST POINT PC MINI .040\"D RED")
      (fields (field (name "MFG") "Keystone"))
      (libsource (lib "HTT SoM - Sept 7 2016 V1P2 ") (part "TP"))
    )
    (comp (ref "TP10")
      (value "Test Point")
      (footprint "TEST_POINT_SMD_30D")
      (description "TEST POINT PC MINI .040\"D RED")
      (fields (field (name "MFG") "Keystone"))
      (libsource (lib "HTT SoM - Sept 7 2016 V1P2 ") (part "TP"))
    )
    (comp (ref "TP11")
      (value "Test Point")
      (footprint "TEST_POINT_SMD_30D")
      (description "TEST POINT PC MINI .040\"D RED")
      (fields (field (name "MFG") "Keystone"))
      (libsource (lib "HTT SoM - Sept 7 2016 V1P2 ") (part "TP"))
    )
    (comp (ref "U6")
      (value "A7672S")
      (footprint "A7672S")
      (fields (field (name "MF") "SIMCom"))
      (libsource (lib "A7672S") (part "A7672S"))
    )
    (comp (ref "X1")
      (value "EVQ-PE104K")
      (footprint "EVQPE104K")
      (description "Switch Tactile N.O. SPST Rectangular Button J-Bend 0.05A 12VDC 1N SMD T/R")
      (fields (field (name "MOUSER PART NUMBER") "667-EVQ-PE104K"))
      (libsource (lib "EVQ-PE104K") (part "EVQ-PE104K"))
    )
  )
  (nets
    (net (code "2") (name "/MK_IN") (class "Default")
      (node (ref "R79") (pin "1") (pinfunction "1_1") (pintype "passive"))
      (node (ref "U6") (pin "20") (pinfunction "MK_IN_3_20") (pintype "bidirectional"))
    )
    (net (code "3") (name "/RX_1(L)") (class "Default")
      (node (ref "Q5") (pin "2") (pinfunction "S_2") (pintype "passive"))
      (node (ref "R16") (pin "2") (pinfunction "2_2") (pintype "passive"))
    )
    (net (code "4") (name "/TX_1(L)") (class "Default")
      (node (ref "Q2") (pin "2") (pinfunction "S_2") (pintype "passive"))
      (node (ref "R14") (pin "2") (pinfunction "2_2") (pintype "passive"))
    )
    (net (code "5") (name "/UART_RXD") (class "Default")
      (node (ref "R78") (pin "1") (pinfunction "1_1") (pintype "passive"))
      (node (ref "U6") (pin "49") (pinfunction "UART3_RXD_49") (pintype "bidirectional"))
    )
    (net (code "6") (name "/UART_TXD") (class "Default")
      (node (ref "R77") (pin "1") (pinfunction "1_1") (pintype "passive"))
      (node (ref "U6") (pin "50") (pinfunction "UART3_TXD_50") (pintype "bidirectional"))
    )
    (net (code "7") (name "/USB_DN") (class "Default")
      (node (ref "D9") (pin "2") (pinfunction "K_2") (pintype "passive"))
      (node (ref "R66") (pin "2") (pinfunction "2_2") (pintype "passive"))
      (node (ref "R68") (pin "1") (pinfunction "1_1") (pintype "passive"))
      (node (ref "U6") (pin "28") (pinfunction "USB_DM_28") (pintype "bidirectional"))
    )
    (net (code "8") (name "/USB_DP") (class "Default")
      (node (ref "D10") (pin "2") (pinfunction "K_2") (pintype "passive"))
      (node (ref "R67") (pin "2") (pinfunction "2_2") (pintype "passive"))
      (node (ref "R69") (pin "1") (pinfunction "1_1") (pintype "passive"))
      (node (ref "U6") (pin "27") (pinfunction "USB_DP_27") (pintype "bidirectional"))
    )
    (net (code "9") (name "/USIM_CLK") (class "Default")
      (node (ref "D18") (pin "2") (pinfunction "A_2") (pintype "passive"))
      (node (ref "D21") (pin "2") (pinfunction "A_2") (pintype "passive"))
      (node (ref "D22") (pin "2") (pinfunction "A_2") (pintype "passive"))
      (node (ref "R22") (pin "1") (pinfunction "1_1") (pintype "passive"))
      (node (ref "R50") (pin "1") (pinfunction "1_1") (pintype "passive"))
      (node (ref "U6") (pin "32") (pinfunction "USIM1_CLK_32") (pintype "bidirectional"))
    )
    (net (code "10") (name "/USIM_DATA") (class "Default")
      (node (ref "D17") (pin "2") (pinfunction "A_2") (pintype "passive"))
      (node (ref "D20") (pin "2") (pinfunction "A_2") (pintype "passive"))
      (node (ref "R23") (pin "1") (pinfunction "1_1") (pintype "passive"))
      (node (ref "R65") (pin "1") (pinfunction "1_1") (pintype "passive"))
      (node (ref "U6") (pin "31") (pinfunction "USIM1_DATA_31") (pintype "bidirectional"))
    )
    (net (code "11") (name "/USIM_RST") (class "Default")
      (node (ref "D19") (pin "2") (pinfunction "A_2") (pintype "passive"))
      (node (ref "R21") (pin "1") (pinfunction "1_1") (pintype "passive"))
      (node (ref "R53") (pin "1") (pinfunction "1_1") (pintype "passive"))
      (node (ref "U6") (pin "33") (pinfunction "USIM1_RST_33") (pintype "bidirectional"))
    )
    (net (code "12") (name "/USIM_VDD") (class "Default")
      (node (ref "C17") (pin "1") (pinfunction "1_1") (pintype "passive"))
      (node (ref "D16") (pin "2") (pinfunction "A_2") (pintype "passive"))
      (node (ref "D23") (pin "2") (pinfunction "A_2") (pintype "passive"))
      (node (ref "J2") (pin "C1") (pinfunction "VCC_C1") (pintype "power_in"))
      (node (ref "R24") (pin "1") (pinfunction "1_1") (pintype "passive"))
      (node (ref "SIM1") (pin "C1") (pinfunction "VCC_C1") (pintype "power_in"))
      (node (ref "U6") (pin "30") (pinfunction "USIM1_VDD_30") (pintype "bidirectional"))
    )
    (net (code "13") (name "1V8") (class "Default")
      (node (ref "C11") (pin "1") (pinfunction "1_1") (pintype "passive"))
      (node (ref "C13") (pin "2") (pinfunction "2_2") (pintype "passive"))
      (node (ref "C15") (pin "2") (pinfunction "2_2") (pintype "passive"))
      (node (ref "C33") (pin "2") (pinfunction "2_2") (pintype "passive"))
      (node (ref "C34") (pin "2") (pinfunction "2_2") (pintype "passive"))
      (node (ref "D14") (pin "2") (pinfunction "A_2") (pintype "passive"))
      (node (ref "R11") (pin "2") (pinfunction "2_2") (pintype "passive"))
      (node (ref "R17") (pin "1") (pinfunction "1_1") (pintype "passive"))
      (node (ref "R18") (pin "1") (pinfunction "1_1") (pintype "passive"))
      (node (ref "R71") (pin "2") (pinfunction "2_2") (pintype "passive"))
      (node (ref "R75") (pin "2") (pinfunction "2_2") (pintype "passive"))
      (node (ref "R83") (pin "1") (pinfunction "1_1") (pintype "passive"))
      (node (ref "U6") (pin "116") (pinfunction "GNSS_VBKP_116") (pintype "bidirectional"))
      (node (ref "U6") (pin "15") (pinfunction "VDD_1V8_15") (pintype "bidirectional"))
      (node (ref "U6") (pin "97") (pinfunction "1V8_GNSS_97") (pintype "bidirectional"))
    )
    (net (code "14") (name "3V3") (class "Default")
      (node (ref "C12") (pin "2") (pinfunction "2_2") (pintype "passive"))
      (node (ref "Q2") (pin "1") (pinfunction "G_1") (pintype "passive"))
      (node (ref "Q5") (pin "1") (pinfunction "G_1") (pintype "passive"))
      (node (ref "R13") (pin "2") (pinfunction "2_2") (pintype "passive"))
      (node (ref "R14") (pin "1") (pinfunction "1_1") (pintype "passive"))
      (node (ref "R16") (pin "1") (pinfunction "1_1") (pintype "passive"))
    )
    (net (code "15") (name "4V") (class "Default")
      (node (ref "D5") (pin "1") (pinfunction "A_1") (pintype "passive"))
      (node (ref "FB1") (pin "1") (pinfunction "1_1") (pintype "passive"))
      (node (ref "R12") (pin "1") (pinfunction "1_1") (pintype "passive"))
      (node (ref "R15") (pin "1") (pinfunction "1_1") (pintype "passive"))
      (node (ref "R19") (pin "2") (pinfunction "2_2") (pintype "passive"))
    )
    (net (code "16") (name "5V") (class "Default")
      (node (ref "D8") (pin "2") (pinfunction "K_2") (pintype "passive"))
      (node (ref "J3") (pin "1") (pinfunction "VCC_1") (pintype "power_in"))
      (node (ref "U6") (pin "24") (pinfunction "VBUS_24") (pintype "bidirectional"))
    )
    (net (code "17") (name "GND") (class "Default")
      (node (ref "C14") (pin "2") (pinfunction "2_2") (pintype "passive"))
      (node (ref "C15") (pin "1") (pinfunction "1_1") (pintype "passive"))
      (node (ref "C17") (pin "2") (pinfunction "2_2") (pintype "passive"))
      (node (ref "C18") (pin "2") (pinfunction "2_2") (pintype "passive"))
      (node (ref "C19") (pin "1") (pinfunction "1_1") (pintype "passive"))
      (node (ref "C20") (pin "2") (pinfunction "2_2") (pintype "passive"))
      (node (ref "C21") (pin "1") (pinfunction "1_1") (pintype "passive"))
      (node (ref "C22") (pin "2") (pinfunction "2_2") (pintype "passive"))
      (node (ref "C23") (pin "2") (pinfunction "2_2") (pintype "passive"))
      (node (ref "C24") (pin "1") (pinfunction "1_1") (pintype "passive"))
      (node (ref "C25") (pin "1") (pinfunction "1_1") (pintype "passive"))
      (node (ref "C26") (pin "1") (pinfunction "1_1") (pintype "passive"))
      (node (ref "C27") (pin "2") (pinfunction "2_2") (pintype "passive"))
      (node (ref "C28") (pin "2") (pinfunction "2_2") (pintype "passive"))
      (node (ref "C31") (pin "1") (pinfunction "1_1") (pintype "passive"))
      (node (ref "C32") (pin "1") (pinfunction "1_1") (pintype "passive"))
      (node (ref "C33") (pin "1") (pinfunction "1_1") (pintype "passive"))
      (node (ref "C34") (pin "1") (pinfunction "1_1") (pintype "passive"))
      (node (ref "C35") (pin "1") (pinfunction "1_1") (pintype "passive"))
      (node (ref "CN2") (pin "2") (pinfunction "2_2") (pintype "passive"))
      (node (ref "D10") (pin "1") (pinfunction "A_1") (pintype "passive"))
      (node (ref "D11") (pin "1") (pinfunction "1_1") (pintype "passive"))
      (node (ref "D12") (pin "1") (pinfunction "A_1") (pintype "passive"))
      (node (ref "D13") (pin "1") (pinfunction "1_1") (pintype "passive"))
      (node (ref "D15") (pin "1") (pinfunction "A_1") (pintype "passive"))
      (node (ref "D16") (pin "1") (pinfunction "A_1") (pintype "passive"))
      (node (ref "D17") (pin "1") (pinfunction "A_1") (pintype "passive"))
      (node (ref "D18") (pin "1") (pinfunction "A_1") (pintype "passive"))
      (node (ref "D19") (pin "1") (pinfunction "A_1") (pintype "passive"))
      (node (ref "D20") (pin "1") (pinfunction "A_1") (pintype "passive"))
      (node (ref "D21") (pin "1") (pinfunction "A_1") (pintype "passive"))
      (node (ref "D22") (pin "1") (pinfunction "A_1") (pintype "passive"))
      (node (ref "D23") (pin "1") (pinfunction "A_1") (pintype "passive"))
      (node (ref "D5") (pin "2") (pinfunction "A_2") (pintype "passive"))
      (node (ref "D6") (pin "1") (pinfunction "1_1") (pintype "passive"))
      (node (ref "D8") (pin "1") (pinfunction "A_1") (pintype "passive"))
      (node (ref "D9") (pin "1") (pinfunction "A_1") (pintype "passive"))
      (node (ref "J2") (pin "C5") (pinfunction "GND_C5") (pintype "power_in"))
      (node (ref "J2") (pin "S1") (pinfunction "SHIELD_S1") (pintype "passive"))
      (node (ref "J2") (pin "S2") (pinfunction "SHIELD_S2") (pintype "passive"))
      (node (ref "J2") (pin "S3") (pinfunction "SHIELD_S3") (pintype "passive"))
      (node (ref "J2") (pin "S4") (pinfunction "SHIELD_S4") (pintype "passive"))
      (node (ref "J3") (pin "5") (pinfunction "GND_5") (pintype "power_in"))
      (node (ref "J3") (pin "SH1") (pinfunction "SHIELD_SH1") (pintype "passive"))
      (node (ref "J3") (pin "SH2") (pinfunction "SHIELD_SH2") (pintype "passive"))
      (node (ref "J3") (pin "SH3") (pinfunction "SHIELD_SH3") (pintype "passive"))
      (node (ref "J3") (pin "SH4") (pinfunction "SHIELD_SH4") (pintype "passive"))
      (node (ref "J3") (pin "SH5") (pinfunction "SHIELD_SH5") (pintype "passive"))
      (node (ref "J3") (pin "SH6") (pinfunction "SHIELD_SH6") (pintype "passive"))
      (node (ref "J8") (pin "S1") (pinfunction "2_S1") (pintype "passive"))
      (node (ref "J8") (pin "S2") (pinfunction "2_S2") (pintype "passive"))
      (node (ref "J8") (pin "S3") (pinfunction "2_S3") (pintype "passive"))
      (node (ref "J8") (pin "S4") (pinfunction "2_S4") (pintype "passive"))
      (node (ref "J9") (pin "S1") (pinfunction "2_S1") (pintype "passive"))
      (node (ref "J9") (pin "S2") (pinfunction "2_S2") (pintype "passive"))
      (node (ref "J9") (pin "S3") (pinfunction "2_S3") (pintype "passive"))
      (node (ref "J9") (pin "S4") (pinfunction "2_S4") (pintype "passive"))
      (node (ref "Q7") (pin "2") (pinfunction "E_2") (pintype "passive"))
      (node (ref "Q9") (pin "2") (pinfunction "E_2") (pintype "passive"))
      (node (ref "R20") (pin "1") (pinfunction "1_1") (pintype "passive"))
      (node (ref "R73") (pin "2") (pinfunction "2_2") (pintype "passive"))
      (node (ref "R82") (pin "1") (pinfunction "1_1") (pintype "passive"))
      (node (ref "SIM1") (pin "C5") (pinfunction "GND_C5") (pintype "power_in"))
      (node (ref "TP11") (pin "1") (pintype "passive"))
      (node (ref "U6") (pin "2") (pinfunction "GND_1_2") (pintype "bidirectional"))
      (node (ref "U6") (pin "29") (pinfunction "GND_4_29") (pintype "bidirectional"))
      (node (ref "U6") (pin "39") (pinfunction "GND_5_39") (pintype "bidirectional"))
      (node (ref "U6") (pin "45") (pinfunction "GND_6_45") (pintype "bidirectional"))
      (node (ref "U6") (pin "46") (pinfunction "GND_7_46") (pintype "bidirectional"))
      (node (ref "U6") (pin "58") (pinfunction "GND_9_58") (pintype "bidirectional"))
      (node (ref "U6") (pin "59") (pinfunction "GND_10_59") (pintype "bidirectional"))
      (node (ref "U6") (pin "61") (pinfunction "GND_11_61") (pintype "bidirectional"))
      (node (ref "U6") (pin "62") (pinfunction "GND_12_62") (pintype "bidirectional"))
      (node (ref "U6") (pin "63") (pinfunction "GND_13_63") (pintype "bidirectional"))
      (node (ref "U6") (pin "64") (pinfunction "GND_14_64") (pintype "bidirectional"))
      (node (ref "U6") (pin "65") (pinfunction "GND_15_65") (pintype "bidirectional"))
      (node (ref "U6") (pin "69") (pinfunction "GND_16_69") (pintype "bidirectional"))
      (node (ref "U6") (pin "70") (pinfunction "GND_17_70") (pintype "bidirectional"))
      (node (ref "U6") (pin "71") (pinfunction "GND_18_71") (pintype "bidirectional"))
      (node (ref "U6") (pin "72") (pinfunction "GND_19_72") (pintype "bidirectional"))
      (node (ref "U6") (pin "73") (pinfunction "GND_20_73") (pintype "bidirectional"))
      (node (ref "U6") (pin "74") (pinfunction "GND_21_74") (pintype "bidirectional"))
      (node (ref "U6") (pin "75") (pinfunction "GND_22_75") (pintype "bidirectional"))
      (node (ref "U6") (pin "76") (pinfunction "GND_23_76") (pintype "bidirectional"))
      (node (ref "U6") (pin "77") (pinfunction "GND_24_77") (pintype "bidirectional"))
      (node (ref "U6") (pin "78") (pinfunction "GND_25_78") (pintype "bidirectional"))
      (node (ref "U6") (pin "79") (pinfunction "GND_26_79") (pintype "bidirectional"))
      (node (ref "U6") (pin "80") (pinfunction "GND_27_80") (pintype "bidirectional"))
      (node (ref "U6") (pin "81") (pinfunction "GND_28_81") (pintype "bidirectional"))
      (node (ref "U6") (pin "82") (pinfunction "GND_29_82") (pintype "bidirectional"))
      (node (ref "U6") (pin "83") (pinfunction "GND_30_83") (pintype "bidirectional"))
      (node (ref "U6") (pin "84") (pinfunction "GND_31_84") (pintype "bidirectional"))
      (node (ref "U6") (pin "85") (pinfunction "GND_32_85") (pintype "bidirectional"))
      (node (ref "U6") (pin "86") (pinfunction "GND_33_86") (pintype "bidirectional"))
      (node (ref "U6") (pin "87") (pinfunction "GND_34_87") (pintype "bidirectional"))
      (node (ref "U6") (pin "88") (pinfunction "GND_35_88") (pintype "bidirectional"))
      (node (ref "U6") (pin "89") (pinfunction "GND_36_89") (pintype "bidirectional"))
      (node (ref "U6") (pin "91") (pinfunction "GND_37_91") (pintype "bidirectional"))
      (node (ref "U6") (pin "92") (pinfunction "GND_38_92") (pintype "bidirectional"))
      (node (ref "X1") (pin "B1") (pinfunction "COM_B1") (pintype "passive"))
    )
    (net (code "18") (name "Net-(C16-Pad1)") (class "Default")
      (node (ref "C16") (pin "1") (pinfunction "1_1") (pintype "passive"))
      (node (ref "C32") (pin "2") (pinfunction "2_2") (pintype "passive"))
      (node (ref "R76") (pin "2") (pinfunction "2_2") (pintype "passive"))
    )
    (net (code "19") (name "Net-(C16-Pad2)") (class "Default")
      (node (ref "C16") (pin "2") (pinfunction "2_2") (pintype "passive"))
      (node (ref "D13") (pin "2") (pinfunction "2_2") (pintype "passive"))
      (node (ref "J8") (pin "1") (pinfunction "1_1") (pintype "passive"))
      (node (ref "L1") (pin "1") (pinfunction "1_1") (pintype "passive"))
    )
    (net (code "20") (name "Net-(C27-Pad1)") (class "Default")
      (node (ref "C27") (pin "1") (pinfunction "1_1") (pintype "passive"))
      (node (ref "R25") (pin "1") (pinfunction "1_1") (pintype "passive"))
      (node (ref "R26") (pin "2") (pinfunction "2_2") (pintype "passive"))
    )
    (net (code "21") (name "Net-(C28-Pad1)") (class "Default")
      (node (ref "C28") (pin "1") (pinfunction "1_1") (pintype "passive"))
      (node (ref "J9") (pin "1") (pinfunction "1_1") (pintype "passive"))
      (node (ref "R25") (pin "2") (pinfunction "2_2") (pintype "passive"))
    )
    (net (code "22") (name "Net-(D12-K)") (class "Default")
      (node (ref "CN2") (pin "1") (pinfunction "1_1") (pintype "passive"))
      (node (ref "D12") (pin "2") (pinfunction "K_2") (pintype "passive"))
      (node (ref "R74") (pin "2") (pinfunction "2_2") (pintype "passive"))
    )
    (net (code "23") (name "Net-(D14-C)") (class "Default")
      (node (ref "D14") (pin "1") (pinfunction "C_1") (pintype "passive"))
      (node (ref "R80") (pin "1") (pinfunction "1_1") (pintype "passive"))
    )
    (net (code "24") (name "Net-(D15-K)") (class "Default")
      (node (ref "C35") (pin "2") (pinfunction "2_2") (pintype "passive"))
      (node (ref "D15") (pin "2") (pinfunction "K_2") (pintype "passive"))
      (node (ref "R83") (pin "2") (pinfunction "2_2") (pintype "passive"))
    )
    (net (code "25") (name "Net-(J2-CLK)") (class "Default")
      (node (ref "J2") (pin "C3") (pinfunction "CLK_C3") (pintype "input"))
      (node (ref "R50") (pin "2") (pinfunction "2_2") (pintype "passive"))
    )
    (net (code "26") (name "Net-(J2-I{slash}O)") (class "Default")
      (node (ref "J2") (pin "C7") (pinfunction "I/O_C7") (pintype "bidirectional"))
      (node (ref "R65") (pin "2") (pinfunction "2_2") (pintype "passive"))
    )
    (net (code "27") (name "Net-(J2-RST)") (class "Default")
      (node (ref "J2") (pin "C2") (pinfunction "RST_C2") (pintype "input"))
      (node (ref "R53") (pin "2") (pinfunction "2_2") (pintype "passive"))
    )
    (net (code "28") (name "Net-(J3-D+)") (class "Default")
      (node (ref "J3") (pin "3") (pinfunction "D+_3") (pintype "passive"))
      (node (ref "R67") (pin "1") (pinfunction "1_1") (pintype "passive"))
    )
    (net (code "29") (name "Net-(J3-D-)") (class "Default")
      (node (ref "J3") (pin "2") (pinfunction "D-_2") (pintype "passive"))
      (node (ref "R66") (pin "1") (pinfunction "1_1") (pintype "passive"))
    )
    (net (code "30") (name "Net-(L1-Pad2)") (class "Default")
      (node (ref "L1") (pin "2") (pinfunction "2_2") (pintype "passive"))
      (node (ref "R75") (pin "1") (pinfunction "1_1") (pintype "passive"))
    )
    (net (code "31") (name "Net-(Q3-B)") (class "Default")
      (node (ref "C11") (pin "2") (pinfunction "2_2") (pintype "passive"))
      (node (ref "Q3") (pin "1") (pinfunction "B_1") (pintype "passive"))
      (node (ref "R11") (pin "1") (pinfunction "1_1") (pintype "passive"))
    )
    (net (code "32") (name "Net-(Q3-E)") (class "Default")
      (node (ref "Q3") (pin "3") (pinfunction "E_3") (pintype "passive"))
      (node (ref "U6") (pin "9") (pinfunction "TXD_9") (pintype "bidirectional"))
    )
    (net (code "33") (name "Net-(Q4-B)") (class "Default")
      (node (ref "C13") (pin "1") (pinfunction "1_1") (pintype "passive"))
      (node (ref "Q4") (pin "1") (pinfunction "B_1") (pintype "passive"))
      (node (ref "R18") (pin "2") (pinfunction "2_2") (pintype "passive"))
    )
    (net (code "34") (name "Net-(Q4-C)") (class "Default")
      (node (ref "Q4") (pin "4") (pinfunction "C_4") (pintype "passive"))
      (node (ref "R17") (pin "2") (pinfunction "2_2") (pintype "passive"))
      (node (ref "U6") (pin "10") (pinfunction "RXD_10") (pintype "bidirectional"))
    )
    (net (code "35") (name "Net-(Q7-B)") (class "Default")
      (node (ref "Q7") (pin "1") (pinfunction "B_1") (pintype "passive"))
      (node (ref "R72") (pin "2") (pinfunction "2_2") (pintype "passive"))
      (node (ref "R73") (pin "1") (pinfunction "1_1") (pintype "passive"))
    )
    (net (code "36") (name "Net-(Q7-C)") (class "Default")
      (node (ref "D11") (pin "2") (pinfunction "2_2") (pintype "passive"))
      (node (ref "Q7") (pin "3") (pinfunction "C_3") (pintype "passive"))
      (node (ref "R70") (pin "1") (pinfunction "1_1") (pintype "passive"))
    )
    (net (code "37") (name "Net-(Q9-B)") (class "Default")
      (node (ref "Q9") (pin "1") (pinfunction "B_1") (pintype "passive"))
      (node (ref "R81") (pin "2") (pinfunction "2_2") (pintype "passive"))
      (node (ref "R82") (pin "2") (pinfunction "2_2") (pintype "passive"))
    )
    (net (code "38") (name "Net-(Q9-C)") (class "Default")
      (node (ref "Q9") (pin "3") (pinfunction "C_3") (pintype "passive"))
      (node (ref "R80") (pin "2") (pinfunction "2_2") (pintype "passive"))
    )
    (net (code "39") (name "Net-(R68-Pad2)") (class "Default")
      (node (ref "R68") (pin "2") (pinfunction "2_2") (pintype "passive"))
      (node (ref "TP9") (pin "1") (pintype "passive"))
    )
    (net (code "40") (name "Net-(R69-Pad2)") (class "Default")
      (node (ref "R69") (pin "2") (pinfunction "2_2") (pintype "passive"))
      (node (ref "TP10") (pin "1") (pintype "passive"))
    )
    (net (code "41") (name "Net-(SIM1-CLK)") (class "Default")
      (node (ref "C25") (pin "2") (pinfunction "2_2") (pintype "passive"))
      (node (ref "R22") (pin "2") (pinfunction "2_2") (pintype "passive"))
      (node (ref "SIM1") (pin "C3") (pinfunction "CLK_C3") (pintype "input"))
    )
    (net (code "42") (name "Net-(SIM1-IO)") (class "Default")
      (node (ref "C26") (pin "2") (pinfunction "2_2") (pintype "passive"))
      (node (ref "R23") (pin "2") (pinfunction "2_2") (pintype "passive"))
      (node (ref "R24") (pin "2") (pinfunction "2_2") (pintype "passive"))
      (node (ref "SIM1") (pin "C7") (pinfunction "IO_C7") (pintype "bidirectional"))
    )
    (net (code "43") (name "Net-(SIM1-RESET)") (class "Default")
      (node (ref "C24") (pin "2") (pinfunction "2_2") (pintype "passive"))
      (node (ref "R21") (pin "2") (pinfunction "2_2") (pintype "passive"))
      (node (ref "SIM1") (pin "C2") (pinfunction "RESET_C2") (pintype "input"))
    )
    (net (code "44") (name "Net-(U6-ADC)") (class "Default")
      (node (ref "C14") (pin "1") (pinfunction "1_1") (pintype "passive"))
      (node (ref "R19") (pin "1") (pinfunction "1_1") (pintype "passive"))
      (node (ref "R20") (pin "2") (pinfunction "2_2") (pintype "passive"))
      (node (ref "U6") (pin "25") (pinfunction "ADC_25") (pintype "bidirectional"))
    )
    (net (code "45") (name "Net-(U6-GNSS_ANT)") (class "Default")
      (node (ref "C31") (pin "2") (pinfunction "2_2") (pintype "passive"))
      (node (ref "R76") (pin "1") (pinfunction "1_1") (pintype "passive"))
      (node (ref "U6") (pin "90") (pinfunction "GNSS_ANT_90") (pintype "bidirectional"))
    )
    (net (code "46") (name "Net-(U6-GNSS_PWRCTL)") (class "Default")
      (node (ref "R79") (pin "2") (pinfunction "2_2") (pintype "passive"))
      (node (ref "U6") (pin "98") (pinfunction "GNSS_PWRCTL_98") (pintype "bidirectional"))
    )
    (net (code "47") (name "Net-(U6-GNSS_RXD)") (class "Default")
      (node (ref "R77") (pin "2") (pinfunction "2_2") (pintype "passive"))
      (node (ref "U6") (pin "96") (pinfunction "GNSS_RXD_96") (pintype "bidirectional"))
    )
    (net (code "48") (name "Net-(U6-GNSS_TXD)") (class "Default")
      (node (ref "R78") (pin "2") (pinfunction "2_2") (pintype "passive"))
      (node (ref "U6") (pin "95") (pinfunction "GNSS_TXD_95") (pintype "bidirectional"))
    )
    (net (code "49") (name "Net-(U6-NETLIGHT)") (class "Default")
      (node (ref "R81") (pin "1") (pinfunction "1_1") (pintype "passive"))
      (node (ref "U6") (pin "52") (pinfunction "NETLIGHT_52") (pintype "bidirectional"))
    )
    (net (code "50") (name "Net-(U6-PWRKEY)") (class "Default")
      (node (ref "R72") (pin "1") (pinfunction "1_1") (pintype "passive"))
      (node (ref "U6") (pin "1") (pinfunction "PWRKEY_1") (pintype "bidirectional"))
    )
    (net (code "51") (name "Net-(U6-RF_ANT)") (class "Default")
      (node (ref "D6") (pin "2") (pinfunction "2_2") (pintype "passive"))
      (node (ref "R26") (pin "1") (pinfunction "1_1") (pintype "passive"))
      (node (ref "U6") (pin "60") (pinfunction "RF_ANT_60") (pintype "bidirectional"))
    )
    (net (code "52") (name "Net-(U6-USB_BOOT)") (class "Default")
      (node (ref "R74") (pin "1") (pinfunction "1_1") (pintype "passive"))
      (node (ref "U6") (pin "6") (pinfunction "USB_BOOT_6") (pintype "bidirectional"))
    )
    (net (code "53") (name "Net-(U6-VBAT_1)") (class "Default")
      (node (ref "C18") (pin "1") (pinfunction "1_1") (pintype "passive"))
      (node (ref "C19") (pin "2") (pinfunction "2_2") (pintype "passive"))
      (node (ref "C20") (pin "1") (pinfunction "1_1") (pintype "passive"))
      (node (ref "C21") (pin "2") (pinfunction "2_2") (pintype "passive"))
      (node (ref "C22") (pin "1") (pinfunction "1_1") (pintype "passive"))
      (node (ref "C23") (pin "1") (pinfunction "1_1") (pintype "passive"))
      (node (ref "FB1") (pin "2") (pinfunction "2_2") (pintype "passive"))
      (node (ref "U6") (pin "55") (pinfunction "VBAT_1_55") (pintype "bidirectional"))
      (node (ref "U6") (pin "56") (pinfunction "VBAT_2_56") (pintype "bidirectional"))
      (node (ref "U6") (pin "57") (pinfunction "VBAT_3_57") (pintype "bidirectional"))
    )
    (net (code "54") (name "Net-(X1-NO)") (class "Default")
      (node (ref "R70") (pin "2") (pinfunction "2_2") (pintype "passive"))
      (node (ref "R71") (pin "1") (pinfunction "1_1") (pintype "passive"))
      (node (ref "X1") (pin "A1") (pinfunction "NO_A1") (pintype "passive"))
    )
    (net (code "55") (name "RX_1(H)") (class "Default")
      (node (ref "C12") (pin "1") (pinfunction "1_1") (pintype "passive"))
      (node (ref "Q3") (pin "4") (pinfunction "C_4") (pintype "passive"))
      (node (ref "Q5") (pin "3") (pinfunction "D_3") (pintype "passive"))
      (node (ref "R13") (pin "1") (pinfunction "1_1") (pintype "passive"))
      (node (ref "R15") (pin "2") (pinfunction "2_2") (pintype "passive"))
    )
    (net (code "56") (name "TX_1(H)") (class "Default")
      (node (ref "Q2") (pin "3") (pinfunction "D_3") (pintype "passive"))
      (node (ref "Q4") (pin "3") (pinfunction "E_3") (pintype "passive"))
      (node (ref "R12") (pin "2") (pinfunction "2_2") (pintype "passive"))
    )
    (net (code "57") (name "unconnected-(J2-PadCD)") (class "Default")
      (node (ref "J2") (pin "CD") (pinfunction "CD_CD") (pintype "passive"))
    )
    (net (code "58") (name "unconnected-(J2-VPP-PadC6)") (class "Default")
      (node (ref "J2") (pin "C6") (pinfunction "VPP_C6") (pintype "power_in"))
    )
    (net (code "59") (name "unconnected-(J3-ID-Pad4)") (class "Default")
      (node (ref "J3") (pin "4") (pinfunction "ID_4") (pintype "passive"))
    )
    (net (code "60") (name "unconnected-(SIM1-PadSW1)") (class "Default")
      (node (ref "SIM1") (pin "SW1") (pinfunction "SW1_SW1") (pintype "bidirectional"))
    )
    (net (code "61") (name "unconnected-(SIM1-PadSW2)") (class "Default")
      (node (ref "SIM1") (pin "SW2") (pinfunction "SW2_SW2") (pintype "bidirectional"))
    )
    (net (code "62") (name "unconnected-(SIM1-VPP-PadC6)") (class "Default")
      (node (ref "SIM1") (pin "C6") (pinfunction "VPP_C6") (pintype "power_in"))
    )
    (net (code "63") (name "unconnected-(U6-1PPS-Pad100)") (class "Default")
      (node (ref "U6") (pin "100") (pinfunction "1PPS_100") (pintype "bidirectional"))
    )
    (net (code "64") (name "unconnected-(U6-BT_ANT-Pad93)") (class "Default")
      (node (ref "U6") (pin "93") (pinfunction "BT_ANT_93") (pintype "bidirectional"))
    )
    (net (code "65") (name "unconnected-(U6-CAM_I2C_SCL-Pad118)") (class "Default")
      (node (ref "U6") (pin "118") (pinfunction "CAM_I2C_SCL_118") (pintype "bidirectional"))
    )
    (net (code "66") (name "unconnected-(U6-CAM_I2C_SDA-Pad117)") (class "Default")
      (node (ref "U6") (pin "117") (pinfunction "CAM_I2C_SDA_117") (pintype "bidirectional"))
    )
    (net (code "67") (name "unconnected-(U6-CAM_MCLK-Pad121)") (class "Default")
      (node (ref "U6") (pin "121") (pinfunction "CAM_MCLK_121") (pintype "bidirectional"))
    )
    (net (code "68") (name "unconnected-(U6-CAM_PWDN-Pad119)") (class "Default")
      (node (ref "U6") (pin "119") (pinfunction "CAM_PWDN_119") (pintype "bidirectional"))
    )
    (net (code "69") (name "unconnected-(U6-CAM_RST-Pad120)") (class "Default")
      (node (ref "U6") (pin "120") (pinfunction "CAM_RST_120") (pintype "bidirectional"))
    )
    (net (code "70") (name "unconnected-(U6-CAM_SPI_CLK-Pad124)") (class "Default")
      (node (ref "U6") (pin "124") (pinfunction "CAM_SPI_CLK_124") (pintype "bidirectional"))
    )
    (net (code "71") (name "unconnected-(U6-CAM_SPI_D0-Pad122)") (class "Default")
      (node (ref "U6") (pin "122") (pinfunction "CAM_SPI_D0_122") (pintype "bidirectional"))
    )
    (net (code "72") (name "unconnected-(U6-CAM_SPI_D1-Pad123)") (class "Default")
      (node (ref "U6") (pin "123") (pinfunction "CAM_SPI_D1_123") (pintype "bidirectional"))
    )
    (net (code "73") (name "unconnected-(U6-CTS-Pad7)") (class "Default")
      (node (ref "U6") (pin "7") (pinfunction "CTS_7") (pintype "bidirectional"))
    )
    (net (code "74") (name "unconnected-(U6-DCD-Pad5)") (class "Default")
      (node (ref "U6") (pin "5") (pinfunction "DCD_5") (pintype "bidirectional"))
    )
    (net (code "75") (name "unconnected-(U6-DTR-Pad3)") (class "Default")
      (node (ref "U6") (pin "3") (pinfunction "DTR_3") (pintype "bidirectional"))
    )
    (net (code "76") (name "unconnected-(U6-EAR_N-Pad41)") (class "Default")
      (node (ref "U6") (pin "41") (pinfunction "EAR_N_41") (pintype "bidirectional"))
    )
    (net (code "77") (name "unconnected-(U6-EAR_P-Pad40)") (class "Default")
      (node (ref "U6") (pin "40") (pinfunction "EAR_P_40") (pintype "bidirectional"))
    )
    (net (code "78") (name "unconnected-(U6-GND_2-Pad17)") (class "Default")
      (node (ref "U6") (pin "17") (pinfunction "GND_2_17") (pintype "bidirectional"))
    )
    (net (code "79") (name "unconnected-(U6-GND_3-Pad18)") (class "Default")
      (node (ref "U6") (pin "18") (pinfunction "GND_3_18") (pintype "bidirectional"))
    )
    (net (code "80") (name "unconnected-(U6-GND_8-Pad54)") (class "Default")
      (node (ref "U6") (pin "54") (pinfunction "GND_8_54") (pintype "bidirectional"))
    )
    (net (code "81") (name "unconnected-(U6-GND_39-Pad94)") (class "Default")
      (node (ref "U6") (pin "94") (pinfunction "GND_39_94") (pintype "bidirectional"))
    )
    (net (code "82") (name "unconnected-(U6-GPIO1-Pad19)") (class "Default")
      (node (ref "U6") (pin "19") (pinfunction "GPIO1_19") (pintype "bidirectional"))
    )
    (net (code "83") (name "unconnected-(U6-GPIO2-Pad26)") (class "Default")
      (node (ref "U6") (pin "26") (pinfunction "GPIO2_26") (pintype "bidirectional"))
    )
    (net (code "84") (name "unconnected-(U6-GPIO3-Pad48)") (class "Default")
      (node (ref "U6") (pin "48") (pinfunction "GPIO3_48") (pintype "bidirectional"))
    )
    (net (code "85") (name "unconnected-(U6-GPIO4-Pad53)") (class "Default")
      (node (ref "U6") (pin "53") (pinfunction "GPIO4_53") (pintype "bidirectional"))
    )
    (net (code "86") (name "unconnected-(U6-I2C_SCL-Pad38)") (class "Default")
      (node (ref "U6") (pin "38") (pinfunction "I2C_SCL_38") (pintype "bidirectional"))
    )
    (net (code "87") (name "unconnected-(U6-I2C_SDA-Pad37)") (class "Default")
      (node (ref "U6") (pin "37") (pinfunction "I2C_SDA_37") (pintype "bidirectional"))
    )
    (net (code "88") (name "unconnected-(U6-LCD_BL_PWM-Pad101)") (class "Default")
      (node (ref "U6") (pin "101") (pinfunction "LCD_BL_PWM_101") (pintype "bidirectional"))
    )
    (net (code "89") (name "unconnected-(U6-LCD_DCX-Pad107)") (class "Default")
      (node (ref "U6") (pin "107") (pinfunction "LCD_DCX_107") (pintype "bidirectional"))
    )
    (net (code "90") (name "unconnected-(U6-LCD_RST-Pad106)") (class "Default")
      (node (ref "U6") (pin "106") (pinfunction "LCD_RST_106") (pintype "bidirectional"))
    )
    (net (code "91") (name "unconnected-(U6-LCD_SPI_CLK-Pad102)") (class "Default")
      (node (ref "U6") (pin "102") (pinfunction "LCD_SPI_CLK_102") (pintype "bidirectional"))
    )
    (net (code "92") (name "unconnected-(U6-LCD_SPI_CS-Pad105)") (class "Default")
      (node (ref "U6") (pin "105") (pinfunction "LCD_SPI_CS_105") (pintype "bidirectional"))
    )
    (net (code "93") (name "unconnected-(U6-LCD_SPI_RXD-Pad104)") (class "Default")
      (node (ref "U6") (pin "104") (pinfunction "LCD_SPI_RXD_104") (pintype "bidirectional"))
    )
    (net (code "94") (name "unconnected-(U6-LCD_SPI_TXD-Pad103)") (class "Default")
      (node (ref "U6") (pin "103") (pinfunction "LCD_SPI_TXD_103") (pintype "bidirectional"))
    )
    (net (code "95") (name "unconnected-(U6-MIC_N-Pad43)") (class "Default")
      (node (ref "U6") (pin "43") (pinfunction "MIC_N_43") (pintype "bidirectional"))
    )
    (net (code "96") (name "unconnected-(U6-MIC_P-Pad42)") (class "Default")
      (node (ref "U6") (pin "42") (pinfunction "MIC_P_42") (pintype "bidirectional"))
    )
    (net (code "97") (name "unconnected-(U6-MK_IN_2-Pad47)") (class "Default")
      (node (ref "U6") (pin "47") (pinfunction "MK_IN_2_47") (pintype "bidirectional"))
    )
    (net (code "98") (name "unconnected-(U6-MK_IN_5-Pad68)") (class "Default")
      (node (ref "U6") (pin "68") (pinfunction "MK_IN_5_68") (pintype "bidirectional"))
    )
    (net (code "99") (name "unconnected-(U6-MK_IN_6{slash}I2C3_SCL-Pad36)") (class "Default")
      (node (ref "U6") (pin "36") (pinfunction "MK_IN_6/I2C3_SCL_36") (pintype "bidirectional"))
    )
    (net (code "100") (name "unconnected-(U6-MK_OUT_2-Pad44)") (class "Default")
      (node (ref "U6") (pin "44") (pinfunction "MK_OUT_2_44") (pintype "bidirectional"))
    )
    (net (code "101") (name "unconnected-(U6-MK_OUT_3-Pad21)") (class "Default")
      (node (ref "U6") (pin "21") (pinfunction "MK_OUT_3_21") (pintype "bidirectional"))
    )
    (net (code "102") (name "unconnected-(U6-MK_OUT_5-Pad67)") (class "Default")
      (node (ref "U6") (pin "67") (pinfunction "MK_OUT_5_67") (pintype "bidirectional"))
    )
    (net (code "103") (name "unconnected-(U6-MK_OUT_6{slash}I2C3_SDA-Pad35)") (class "Default")
      (node (ref "U6") (pin "35") (pinfunction "MK_OUT_6/I2C3_SDA_35") (pintype "bidirectional"))
    )
    (net (code "104") (name "unconnected-(U6-NC_1-Pad113)") (class "Default")
      (node (ref "U6") (pin "113") (pinfunction "NC_1_113") (pintype "bidirectional"))
    )
    (net (code "105") (name "unconnected-(U6-NC_2-Pad114)") (class "Default")
      (node (ref "U6") (pin "114") (pinfunction "NC_2_114") (pintype "bidirectional"))
    )
    (net (code "106") (name "unconnected-(U6-NC_3-Pad115)") (class "Default")
      (node (ref "U6") (pin "115") (pinfunction "NC_3_115") (pintype "bidirectional"))
    )
    (net (code "107") (name "unconnected-(U6-RESET-Pad16)") (class "Default")
      (node (ref "U6") (pin "16") (pinfunction "RESET_16") (pintype "bidirectional"))
    )
    (net (code "108") (name "unconnected-(U6-RI-Pad4)") (class "Default")
      (node (ref "U6") (pin "4") (pinfunction "RI_4") (pintype "bidirectional"))
    )
    (net (code "109") (name "unconnected-(U6-RTS-Pad8)") (class "Default")
      (node (ref "U6") (pin "8") (pinfunction "RTS_8") (pintype "bidirectional"))
    )
    (net (code "110") (name "unconnected-(U6-SPI_CLK-Pad11)") (class "Default")
      (node (ref "U6") (pin "11") (pinfunction "SPI_CLK_11") (pintype "bidirectional"))
    )
    (net (code "111") (name "unconnected-(U6-SPI_CS-Pad12)") (class "Default")
      (node (ref "U6") (pin "12") (pinfunction "SPI_CS_12") (pintype "bidirectional"))
    )
    (net (code "112") (name "unconnected-(U6-SPI_MISO-Pad14)") (class "Default")
      (node (ref "U6") (pin "14") (pinfunction "SPI_MISO_14") (pintype "bidirectional"))
    )
    (net (code "113") (name "unconnected-(U6-SPI_MOSI-Pad13)") (class "Default")
      (node (ref "U6") (pin "13") (pinfunction "SPI_MOSI_13") (pintype "bidirectional"))
    )
    (net (code "114") (name "unconnected-(U6-STATUS-Pad66)") (class "Default")
      (node (ref "U6") (pin "66") (pinfunction "STATUS_66") (pintype "bidirectional"))
    )
    (net (code "115") (name "unconnected-(U6-UART_LOG_RX-Pad22)") (class "Default")
      (node (ref "U6") (pin "22") (pinfunction "UART_LOG_RX_22") (pintype "bidirectional"))
    )
    (net (code "116") (name "unconnected-(U6-UART_LOG_TX-Pad23)") (class "Default")
      (node (ref "U6") (pin "23") (pinfunction "UART_LOG_TX_23") (pintype "bidirectional"))
    )
    (net (code "117") (name "unconnected-(U6-USIM1_DET-Pad34)") (class "Default")
      (node (ref "U6") (pin "34") (pinfunction "USIM1_DET_34") (pintype "bidirectional"))
    )
    (net (code "118") (name "unconnected-(U6-USIM2_CLK-Pad109)") (class "Default")
      (node (ref "U6") (pin "109") (pinfunction "USIM2_CLK_109") (pintype "bidirectional"))
    )
    (net (code "119") (name "unconnected-(U6-USIM2_DATA-Pad108)") (class "Default")
      (node (ref "U6") (pin "108") (pinfunction "USIM2_DATA_108") (pintype "bidirectional"))
    )
    (net (code "120") (name "unconnected-(U6-USIM2_DET-Pad112)") (class "Default")
      (node (ref "U6") (pin "112") (pinfunction "USIM2_DET_112") (pintype "bidirectional"))
    )
    (net (code "121") (name "unconnected-(U6-USIM2_RST-Pad111)") (class "Default")
      (node (ref "U6") (pin "111") (pinfunction "USIM2_RST_111") (pintype "bidirectional"))
    )
    (net (code "122") (name "unconnected-(U6-USIM2_VDD-Pad110)") (class "Default")
      (node (ref "U6") (pin "110") (pinfunction "USIM2_VDD_110") (pintype "bidirectional"))
    )
    (net (code "123") (name "unconnected-(U6-VBAT_ADC-Pad51)") (class "Default")
      (node (ref "U6") (pin "51") (pinfunction "VBAT_ADC_51") (pintype "bidirectional"))
    )
    (net (code "124") (name "unconnected-(U6-VDD_2V8-Pad99)") (class "Default")
      (node (ref "U6") (pin "99") (pinfunction "VDD_2V8_99") (pintype "bidirectional"))
    )
  )
)
